# Rechaza_bandas.net
KiCad netlist of a schematic drawn in Altium Designer
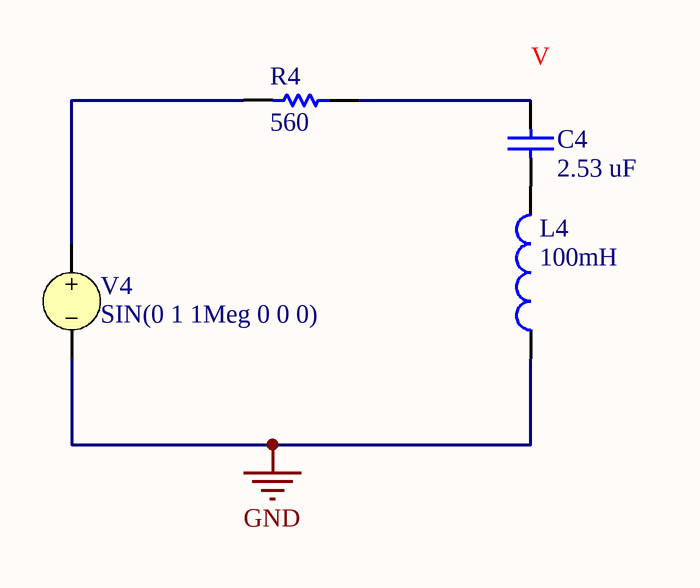
[diagram p0: Rechaza_bandas.SchDoc]

(export (version "E")
  (design (tool "Eeschema 10.0.6"))
  (components
    (comp (ref "C4")
      (value "2.53 uF")
      (description "Capacitor")
      (libsource (lib "Simulation Generic Components") (part "Capacitor"))
    )
    (comp (ref "L4")
      (value "100mH")
      (description "Inductor")
      (libsource (lib "Simulation Generic Components") (part "Inductor"))
    )
    (comp (ref "R4")
      (value "560")
      (description "Resistor")
      (libsource (lib "Simulation Generic Components") (part "Resistor"))
    )
    (comp (ref "V4")
      (value "SIN(0 1 1Meg 0 0 0)")
      (description "Voltage Source")
      (fields (field (name "PUBLISHER") "Altium Limited"))
      (libsource (lib "Simulation Generic Components") (part "VSRC"))
    )
  )
  (nets
    (net (code "1") (name "GND") (class "Default")
      (node (ref "L4") (pin "1") (pinfunction "1_1") (pintype "passive"))
      (node (ref "V4") (pin "2") (pinfunction "2_2") (pintype "passive"))
    )
    (net (code "2") (name "Net-(C4-Pad1)") (class "Default")
      (node (ref "C4") (pin "1") (pinfunction "1_1") (pintype "passive"))
      (node (ref "L4") (pin "2") (pinfunction "2_2") (pintype "passive"))
    )
    (net (code "3") (name "Net-(C4-Pad2)") (class "Default")
      (node (ref "C4") (pin "2") (pinfunction "2_2") (pintype "passive"))
      (node (ref "R4") (pin "1") (pinfunction "1_1") (pintype "passive"))
    )
    (net (code "4") (name "Net-(R4-Pad2)") (class "Default")
      (node (ref "R4") (pin "2") (pinfunction "2_2") (pintype "passive"))
      (node (ref "V4") (pin "1") (pinfunction "1_1") (pintype "passive"))
    )
  )
)
